# Boost_Converter.net
KiCad netlist of a schematic drawn in Altium Designer
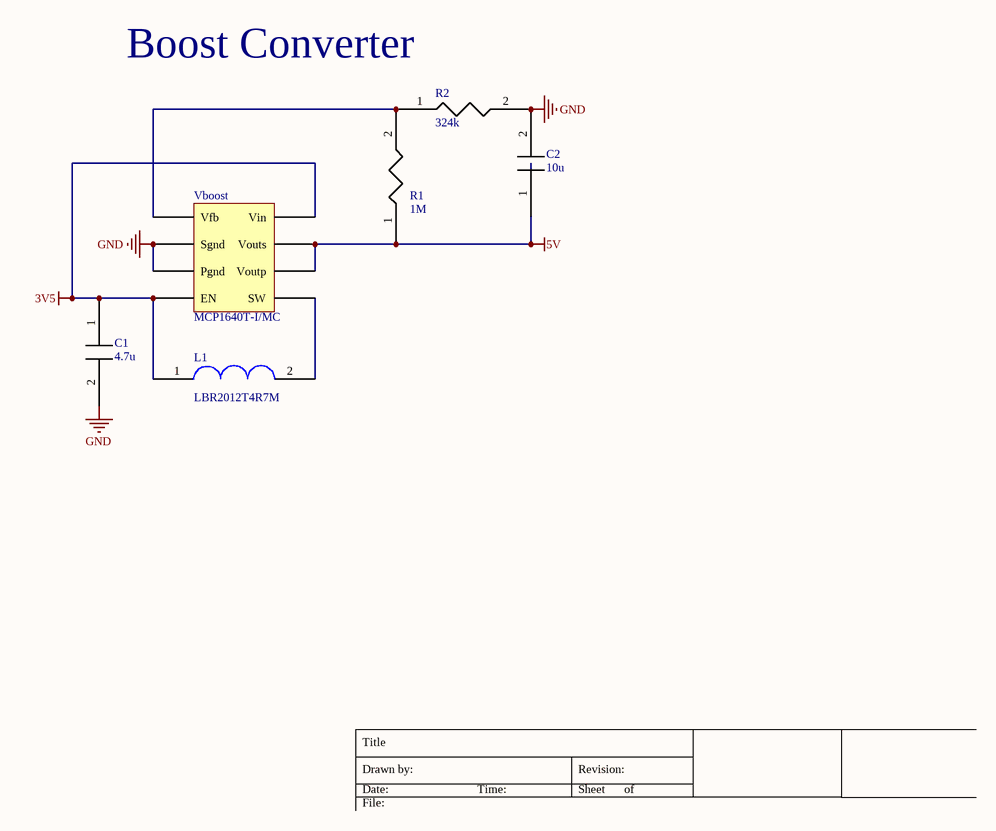
[diagram p0: Boost_Converter.SchDoc]

(export (version "E")
  (design (tool "Eeschema 10.0.6"))
  (components
    (comp (ref "C1")
      (value "4.7u")
      (footprint "Capacitor 0805")
      (libsource (lib "WhereAbles") (part "Capacitor 0805"))
    )
    (comp (ref "C2")
      (value "10u")
      (footprint "Capacitor 0805")
      (libsource (lib "WhereAbles") (part "Capacitor 0805"))
    )
    (comp (ref "L1")
      (value "LBR2012T4R7M")
      (footprint "LBR2012T4R7M")
      (libsource (lib "WhereAbles") (part "LBR2012T4R7M"))
    )
    (comp (ref "R1")
      (value "1M")
      (footprint "Resistor 0403")
      (libsource (lib "WhereAbles") (part "Resistor 0403"))
    )
    (comp (ref "R2")
      (value "324k")
      (footprint "Resistor 0603")
      (libsource (lib "WhereAbles") (part "Resistor 0603"))
    )
    (comp (ref "Vboost")
      (value "MCP1640T-I/MC")
      (footprint "MCP1640T-I/MC")
      (libsource (lib "NaviGo v3.0") (part "MCP1640T-I/MC"))
    )
  )
  (nets
    (net (code "1") (name "3V5") (class "Default")
      (node (ref "C1") (pin "1") (pinfunction "1_1") (pintype "passive"))
      (node (ref "L1") (pin "1") (pinfunction "1_1") (pintype "passive"))
      (node (ref "Vboost") (pin "4") (pinfunction "EN_4") (pintype "passive"))
      (node (ref "Vboost") (pin "8") (pinfunction "Vin_8") (pintype "passive"))
    )
    (net (code "2") (name "5V") (class "Default")
      (node (ref "C2") (pin "1") (pinfunction "1_1") (pintype "passive"))
      (node (ref "R1") (pin "1") (pinfunction "1_1") (pintype "passive"))
      (node (ref "Vboost") (pin "6") (pinfunction "Voutp_6") (pintype "passive"))
      (node (ref "Vboost") (pin "7") (pinfunction "Vouts_7") (pintype "passive"))
    )
    (net (code "3") (name "GND") (class "Default")
      (node (ref "C1") (pin "2") (pinfunction "2_2") (pintype "passive"))
      (node (ref "C2") (pin "2") (pinfunction "2_2") (pintype "passive"))
      (node (ref "R2") (pin "2") (pinfunction "2_2") (pintype "passive"))
      (node (ref "Vboost") (pin "2") (pinfunction "Sgnd_2") (pintype "passive"))
      (node (ref "Vboost") (pin "3") (pinfunction "Pgnd_3") (pintype "passive"))
    )
    (net (code "4") (name "Net-(Vboost-SW)") (class "Default")
      (node (ref "L1") (pin "2") (pinfunction "2_2") (pintype "passive"))
      (node (ref "Vboost") (pin "5") (pinfunction "SW_5") (pintype "passive"))
    )
    (net (code "5") (name "Net-(Vboost-Vfb)") (class "Default")
      (node (ref "R1") (pin "2") (pinfunction "2_2") (pintype "passive"))
      (node (ref "R2") (pin "1") (pinfunction "1_1") (pintype "passive"))
      (node (ref "Vboost") (pin "1") (pinfunction "Vfb_1") (pintype "passive"))
    )
  )
)
